# DC_Circuitry.net
KiCad netlist of a schematic drawn in Altium Designer
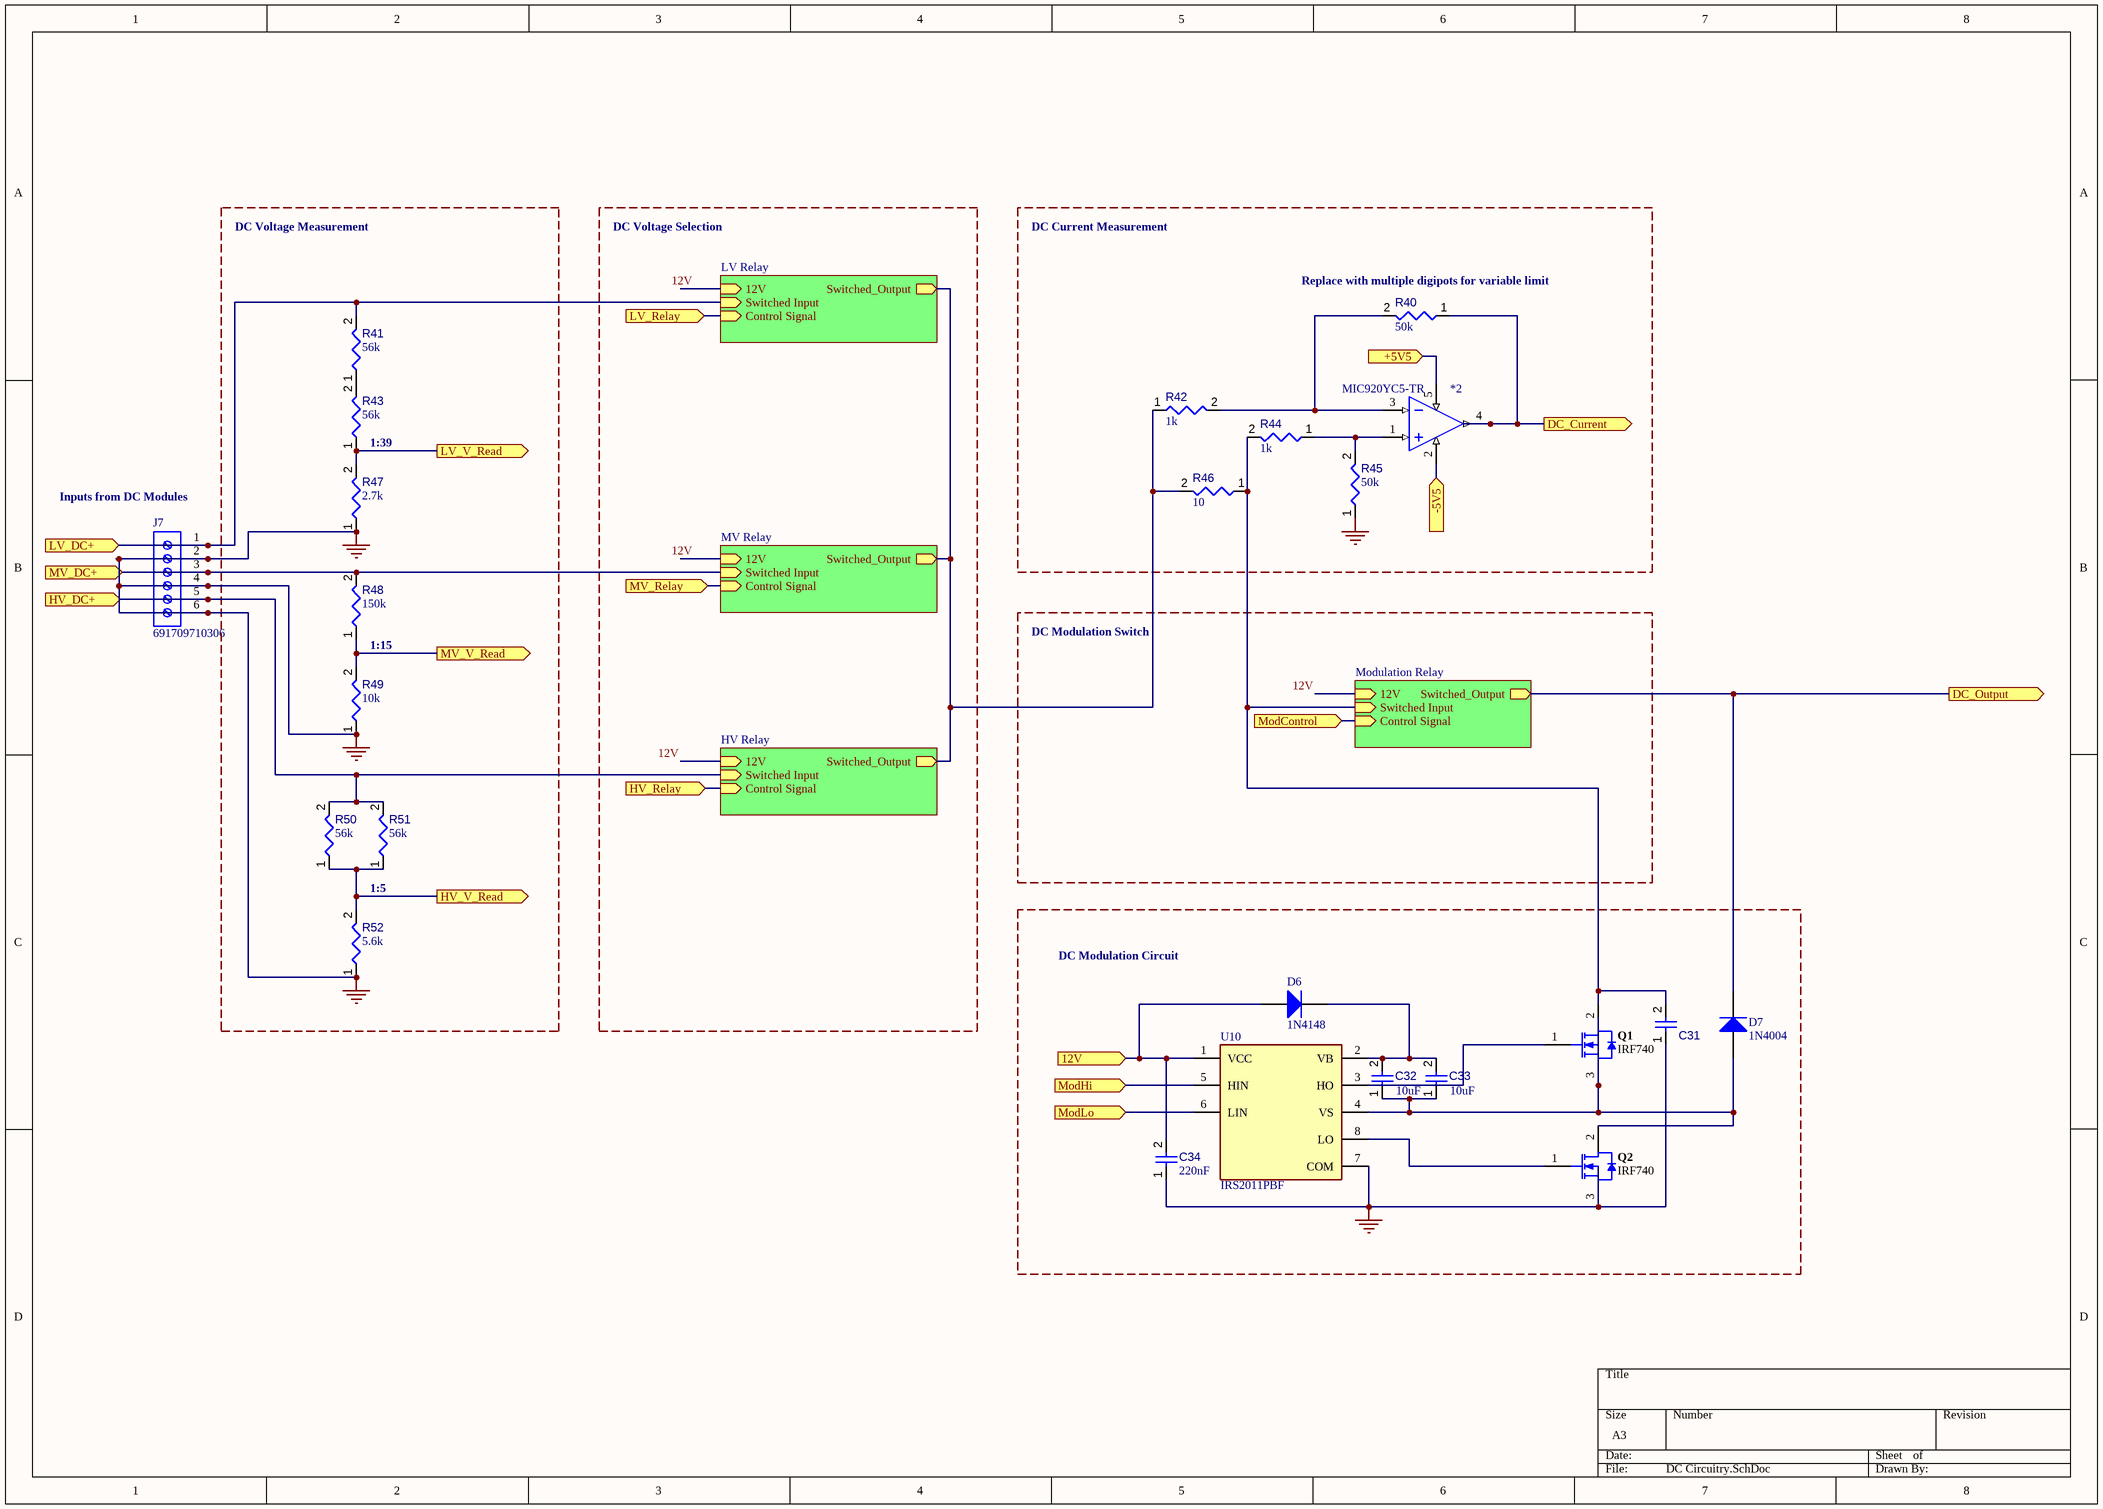
[diagram p0: DC Circuitry.SchDoc]

(export (version "E")
  (design (tool "Eeschema 10.0.6"))
  (components
    (comp (ref "*2")
      (value "MIC920YC5-TR")
      (footprint "SOT65P129X100-6N")
      (description "Operational Amplifier, 1 Func, 5000uV Offset-Max, PDSO5")
      (libsource (lib "University of Western Australia") (part "MIC920YC5-TR-Symbol-1"))
    )
    (comp (ref "C31")
      (value "Capacitors")
      (description "Capacitor")
      (libsource (lib "University of Western Australia") (part "CAP-NP-2"))
    )
    (comp (ref "C32")
      (value "10uF")
      (footprint "FP-C3225-250-0_4-IPC_A")
      (fields (field (name "Comment") "C3225X7R1H106K250AC"))
      (libsource (lib "University of Western Australia") (part "CAP-NP-2"))
    )
    (comp (ref "C33")
      (value "10uF")
      (footprint "FP-C3225-250-0_4-IPC_A")
      (fields (field (name "Comment") "C3225X7R1H106K250AC"))
      (libsource (lib "University of Western Australia") (part "CAP-NP-2"))
    )
    (comp (ref "C34")
      (value "220nF")
      (footprint "FP-C0603C-CF-IPC_B")
      (description "0603 C 220nF Ceramic Multilayer Capacitor; 25 V; +125degC; X7R Dielec; +/-10%")
      (fields (field (name "TOLERANCE") "10%") (field (name "Comment") "C0603C224K3RACTU"))
      (libsource (lib "University of Western Australia") (part "CAP-NP-2"))
    )
    (comp (ref "D6")
      (value "1N4148")
      (footprint "NXP-SOD27-2_V")
      (description "High Speed Diode, 100 V, 0.45 A, -65 to 175 degC, 2-Pin SOD27, RoHS, Bulk")
      (fields (field (name "POWER") "500mW") (field (name "MANUFACTURER") "Fairchild"))
      (libsource (lib "University of Western Australia") (part "D-AK-2"))
    )
    (comp (ref "D7")
      (value "1N4004")
      (footprint "FAIR-DO-41-2")
      (fields (field (name "MANUFACTURER") "Fairchild Semiconductor"))
      (libsource (lib "University of Western Australia") (part "D-AK-2"))
    )
    (comp (ref "J7")
      (value "691709710306")
      (footprint "691709710306")
      (description "WR-TBL Terminal block - Rising Cage - SMT 6 way screw")
      (libsource (lib "University of Western Australia") (part "TBL - 1R - 06P - Screw"))
    )
    (comp (ref "Q1")
      (value "IRF740")
      (footprint "IRF740-Footprint-1")
      (libsource (lib "University of Western Australia") (part "NEMOS-GDS-3"))
    )
    (comp (ref "Q2")
      (value "IRF740")
      (footprint "IRF740-Footprint-1")
      (libsource (lib "University of Western Australia") (part "NEMOS-GDS-3"))
    )
    (comp (ref "R40")
      (value "50k")
      (footprint "FP-MF0207-MFG")
      (description "Fixed Resistor, Metal Film, 0.6W, 10000ohm, 350V, 1% +/-Tol, 50ppm/Cel, Through Hole Mount")
      (fields (field (name "TOLERANCE") "1%") (field (name "Comment") "MF0207FTE52-10K"))
      (libsource (lib "University of Western Australia") (part "RES-2"))
    )
    (comp (ref "R41")
      (value "56k")
      (footprint "FP-MF0207-MFG")
      (description "Fixed Resistor, Metal Film, 0.6W, 10000ohm, 350V, 1% +/-Tol, 50ppm/Cel, Through Hole Mount")
      (fields (field (name "TOLERANCE") "1%") (field (name "Comment") "MF0207FTE52-10K"))
      (libsource (lib "University of Western Australia") (part "RES-2"))
    )
    (comp (ref "R42")
      (value "1k")
      (footprint "RESA60-630X240")
      (description "Fixed Resistor, Metal Film, 0.25W, 1000ohm, 250V, 1% +/-Tol, 100ppm/Cel, Through Hole Mount")
      (fields (field (name "TOLERANCE") "1%") (field (name "POWER") "250mW"))
      (libsource (lib "University of Western Australia") (part "RES-2"))
    )
    (comp (ref "R43")
      (value "56k")
      (footprint "FP-MF0207-MFG")
      (description "Fixed Resistor, Metal Film, 0.6W, 10000ohm, 350V, 1% +/-Tol, 50ppm/Cel, Through Hole Mount")
      (fields (field (name "TOLERANCE") "1%") (field (name "Comment") "MF0207FTE52-10K"))
      (libsource (lib "University of Western Australia") (part "RES-2"))
    )
    (comp (ref "R44")
      (value "1k")
      (footprint "RESA60-630X240")
      (description "Fixed Resistor, Metal Film, 0.25W, 1000ohm, 250V, 1% +/-Tol, 100ppm/Cel, Through Hole Mount")
      (fields (field (name "TOLERANCE") "1%") (field (name "POWER") "250mW"))
      (libsource (lib "University of Western Australia") (part "RES-2"))
    )
    (comp (ref "R45")
      (value "50k")
      (footprint "FP-MF0207-MFG")
      (description "Fixed Resistor, Metal Film, 0.6W, 10000ohm, 350V, 1% +/-Tol, 50ppm/Cel, Through Hole Mount")
      (fields (field (name "TOLERANCE") "1%") (field (name "Comment") "MF0207FTE52-10K"))
      (libsource (lib "University of Western Australia") (part "RES-2"))
    )
    (comp (ref "R46")
      (value "10")
      (footprint "RESC0402(1005)_L")
      (description "Chip Resistor, 10 Ohms, +/-1 %, 63 mW, -55 to 155 degC, 0402")
      (fields (field (name "TOLERANCE") "1%") (field (name "POWER") "63mW"))
      (libsource (lib "University of Western Australia") (part "RES-2"))
    )
    (comp (ref "R47")
      (value "2.7k")
      (footprint "FP-MF0207-MFG")
      (description "Fixed Resistor, Metal Film, 0.6W, 10000ohm, 350V, 1% +/-Tol, 50ppm/Cel, Through Hole Mount")
      (fields (field (name "TOLERANCE") "1%") (field (name "Comment") "MF0207FTE52-10K"))
      (libsource (lib "University of Western Australia") (part "RES-2"))
    )
    (comp (ref "R48")
      (value "150k")
      (footprint "FP-MF0207-MFG")
      (description "Fixed Resistor, Metal Film, 0.6W, 10000ohm, 350V, 1% +/-Tol, 50ppm/Cel, Through Hole Mount")
      (fields (field (name "TOLERANCE") "1%") (field (name "Comment") "MF0207FTE52-10K"))
      (libsource (lib "University of Western Australia") (part "RES-2"))
    )
    (comp (ref "R49")
      (value "10k")
      (footprint "FP-MF0207-MFG")
      (description "Fixed Resistor, Metal Film, 0.6W, 10000ohm, 350V, 1% +/-Tol, 50ppm/Cel, Through Hole Mount")
      (fields (field (name "TOLERANCE") "1%") (field (name "Comment") "MF0207FTE52-10K"))
      (libsource (lib "University of Western Australia") (part "RES-2"))
    )
    (comp (ref "R50")
      (value "56k")
      (footprint "FP-MF0207-MFG")
      (description "Fixed Resistor, Metal Film, 0.6W, 10000ohm, 350V, 1% +/-Tol, 50ppm/Cel, Through Hole Mount")
      (fields (field (name "TOLERANCE") "1%") (field (name "Comment") "MF0207FTE52-10K"))
      (libsource (lib "University of Western Australia") (part "RES-2"))
    )
    (comp (ref "R51")
      (value "56k")
      (footprint "FP-MF0207-MFG")
      (description "Fixed Resistor, Metal Film, 0.6W, 10000ohm, 350V, 1% +/-Tol, 50ppm/Cel, Through Hole Mount")
      (fields (field (name "TOLERANCE") "1%") (field (name "Comment") "MF0207FTE52-10K"))
      (libsource (lib "University of Western Australia") (part "RES-2"))
    )
    (comp (ref "R52")
      (value "5.6k")
      (footprint "FP-MF0207-MFG")
      (description "Fixed Resistor, Metal Film, 0.6W, 10000ohm, 350V, 1% +/-Tol, 50ppm/Cel, Through Hole Mount")
      (fields (field (name "TOLERANCE") "1%") (field (name "Comment") "MF0207FTE52-10K"))
      (libsource (lib "University of Western Australia") (part "RES-2"))
    )
    (comp (ref "U10")
      (value "IRS2011PBF")
      (footprint "FP-PG-DIP-8-MFG")
      (description "Buffer/Inverter Based Peripheral Driver, CMOS, PDIP8")
      (libsource (lib "University of Western Australia") (part "d476b025eeb62b75c63cd295e894faf"))
    )
  )
  (nets
    (net (code "1") (name "/+5V5") (class "Default")
      (node (ref "*2") (pin "5") (pinfunction "V+_5") (pintype "input"))
    )
    (net (code "2") (name "/-5V5") (class "Default")
      (node (ref "*2") (pin "2") (pinfunction "V-_2") (pintype "input"))
    )
    (net (code "3") (name "/12V") (class "Default")
      (node (ref "C34") (pin "2") (pinfunction "2_2") (pintype "passive"))
      (node (ref "D6") (pin "1") (pinfunction "A_1") (pintype "passive"))
      (node (ref "U10") (pin "1") (pinfunction "VCC_1") (pintype "power_in"))
    )
    (net (code "4") (name "/DC_Current") (class "Default")
      (node (ref "*2") (pin "4") (pinfunction "OUT_4") (pintype "output"))
      (node (ref "R40") (pin "1") (pinfunction "1_1") (pintype "passive"))
    )
    (net (code "5") (name "/DC_Output") (class "Default")
      (node (ref "D7") (pin "2") (pinfunction "K_2") (pintype "passive"))
    )
    (net (code "6") (name "/HV_DC+") (class "Default")
      (node (ref "J7") (pin "5") (pinfunction "5_5") (pintype "passive"))
      (node (ref "R50") (pin "2") (pinfunction "2_2") (pintype "passive"))
      (node (ref "R51") (pin "2") (pinfunction "2_2") (pintype "passive"))
    )
    (net (code "8") (name "/HV_V_Read") (class "Default")
      (node (ref "R50") (pin "1") (pinfunction "1_1") (pintype "passive"))
      (node (ref "R51") (pin "1") (pinfunction "1_1") (pintype "passive"))
      (node (ref "R52") (pin "2") (pinfunction "2_2") (pintype "passive"))
    )
    (net (code "9") (name "/LV_DC+") (class "Default")
      (node (ref "J7") (pin "1") (pinfunction "1_1") (pintype "passive"))
      (node (ref "R41") (pin "2") (pinfunction "2_2") (pintype "passive"))
    )
    (net (code "11") (name "/LV_V_Read") (class "Default")
      (node (ref "R43") (pin "1") (pinfunction "1_1") (pintype "passive"))
      (node (ref "R47") (pin "2") (pinfunction "2_2") (pintype "passive"))
    )
    (net (code "12") (name "/MV_DC+") (class "Default")
      (node (ref "J7") (pin "3") (pinfunction "3_3") (pintype "passive"))
      (node (ref "R48") (pin "2") (pinfunction "2_2") (pintype "passive"))
    )
    (net (code "14") (name "/MV_V_Read") (class "Default")
      (node (ref "R48") (pin "1") (pinfunction "1_1") (pintype "passive"))
      (node (ref "R49") (pin "2") (pinfunction "2_2") (pintype "passive"))
    )
    (net (code "16") (name "/ModHi") (class "Default")
      (node (ref "U10") (pin "5") (pinfunction "HIN_5") (pintype "power_in"))
    )
    (net (code "17") (name "/ModLo") (class "Default")
      (node (ref "U10") (pin "6") (pinfunction "LIN_6") (pintype "power_in"))
    )
    (net (code "18") (name "/Switched Input") (class "Default")
      (node (ref "C31") (pin "2") (pinfunction "2_2") (pintype "passive"))
      (node (ref "Q1") (pin "2") (pinfunction "D_2") (pintype "passive"))
      (node (ref "R44") (pin "2") (pinfunction "2_2") (pintype "passive"))
      (node (ref "R46") (pin "1") (pinfunction "1_1") (pintype "passive"))
    )
    (net (code "19") (name "/Switched_Output") (class "Default")
      (node (ref "R42") (pin "1") (pinfunction "1_1") (pintype "passive"))
      (node (ref "R46") (pin "2") (pinfunction "2_2") (pintype "passive"))
    )
    (net (code "20") (name "GND") (class "Default")
      (node (ref "C31") (pin "1") (pinfunction "1_1") (pintype "passive"))
      (node (ref "C34") (pin "1") (pinfunction "1_1") (pintype "passive"))
      (node (ref "J7") (pin "2") (pinfunction "2_2") (pintype "passive"))
      (node (ref "J7") (pin "4") (pinfunction "4_4") (pintype "passive"))
      (node (ref "J7") (pin "6") (pinfunction "6_6") (pintype "passive"))
      (node (ref "Q2") (pin "3") (pinfunction "S_3") (pintype "passive"))
      (node (ref "R45") (pin "1") (pinfunction "1_1") (pintype "passive"))
      (node (ref "R47") (pin "1") (pinfunction "1_1") (pintype "passive"))
      (node (ref "R49") (pin "1") (pinfunction "1_1") (pintype "passive"))
      (node (ref "R52") (pin "1") (pinfunction "1_1") (pintype "passive"))
      (node (ref "U10") (pin "7") (pinfunction "COM_7") (pintype "passive"))
    )
    (net (code "21") (name "Net-(*2-+IN)") (class "Default")
      (node (ref "*2") (pin "1") (pinfunction "+IN_1") (pintype "input"))
      (node (ref "R44") (pin "1") (pinfunction "1_1") (pintype "passive"))
      (node (ref "R45") (pin "2") (pinfunction "2_2") (pintype "passive"))
    )
    (net (code "22") (name "Net-(*2--IN)") (class "Default")
      (node (ref "*2") (pin "3") (pinfunction "-IN_3") (pintype "input"))
      (node (ref "R40") (pin "2") (pinfunction "2_2") (pintype "passive"))
      (node (ref "R42") (pin "2") (pinfunction "2_2") (pintype "passive"))
    )
    (net (code "23") (name "Net-(D6-K)") (class "Default")
      (node (ref "C32") (pin "2") (pinfunction "2_2") (pintype "passive"))
      (node (ref "C33") (pin "2") (pinfunction "2_2") (pintype "passive"))
      (node (ref "D6") (pin "2") (pinfunction "K_2") (pintype "passive"))
      (node (ref "U10") (pin "2") (pinfunction "VB_2") (pintype "passive"))
    )
    (net (code "24") (name "Net-(D7-A)") (class "Default")
      (node (ref "C32") (pin "1") (pinfunction "1_1") (pintype "passive"))
      (node (ref "C33") (pin "1") (pinfunction "1_1") (pintype "passive"))
      (node (ref "D7") (pin "1") (pinfunction "A_1") (pintype "passive"))
      (node (ref "Q1") (pin "3") (pinfunction "S_3") (pintype "passive"))
      (node (ref "Q2") (pin "2") (pinfunction "D_2") (pintype "passive"))
      (node (ref "U10") (pin "4") (pinfunction "VS_4") (pintype "power_in"))
    )
    (net (code "25") (name "Net-(Q1-G)") (class "Default")
      (node (ref "Q1") (pin "1") (pinfunction "G_1") (pintype "passive"))
      (node (ref "U10") (pin "3") (pinfunction "HO_3") (pintype "passive"))
    )
    (net (code "26") (name "Net-(Q2-G)") (class "Default")
      (node (ref "Q2") (pin "1") (pinfunction "G_1") (pintype "passive"))
      (node (ref "U10") (pin "8") (pinfunction "LO_8") (pintype "passive"))
    )
    (net (code "27") (name "Net-(R41-Pad1)") (class "Default")
      (node (ref "R41") (pin "1") (pinfunction "1_1") (pintype "passive"))
      (node (ref "R43") (pin "2") (pinfunction "2_2") (pintype "passive"))
    )
  )
)
